# PAGE2-BLE_POWER_LORA.net
KiCad netlist of a schematic drawn in Altium Designer
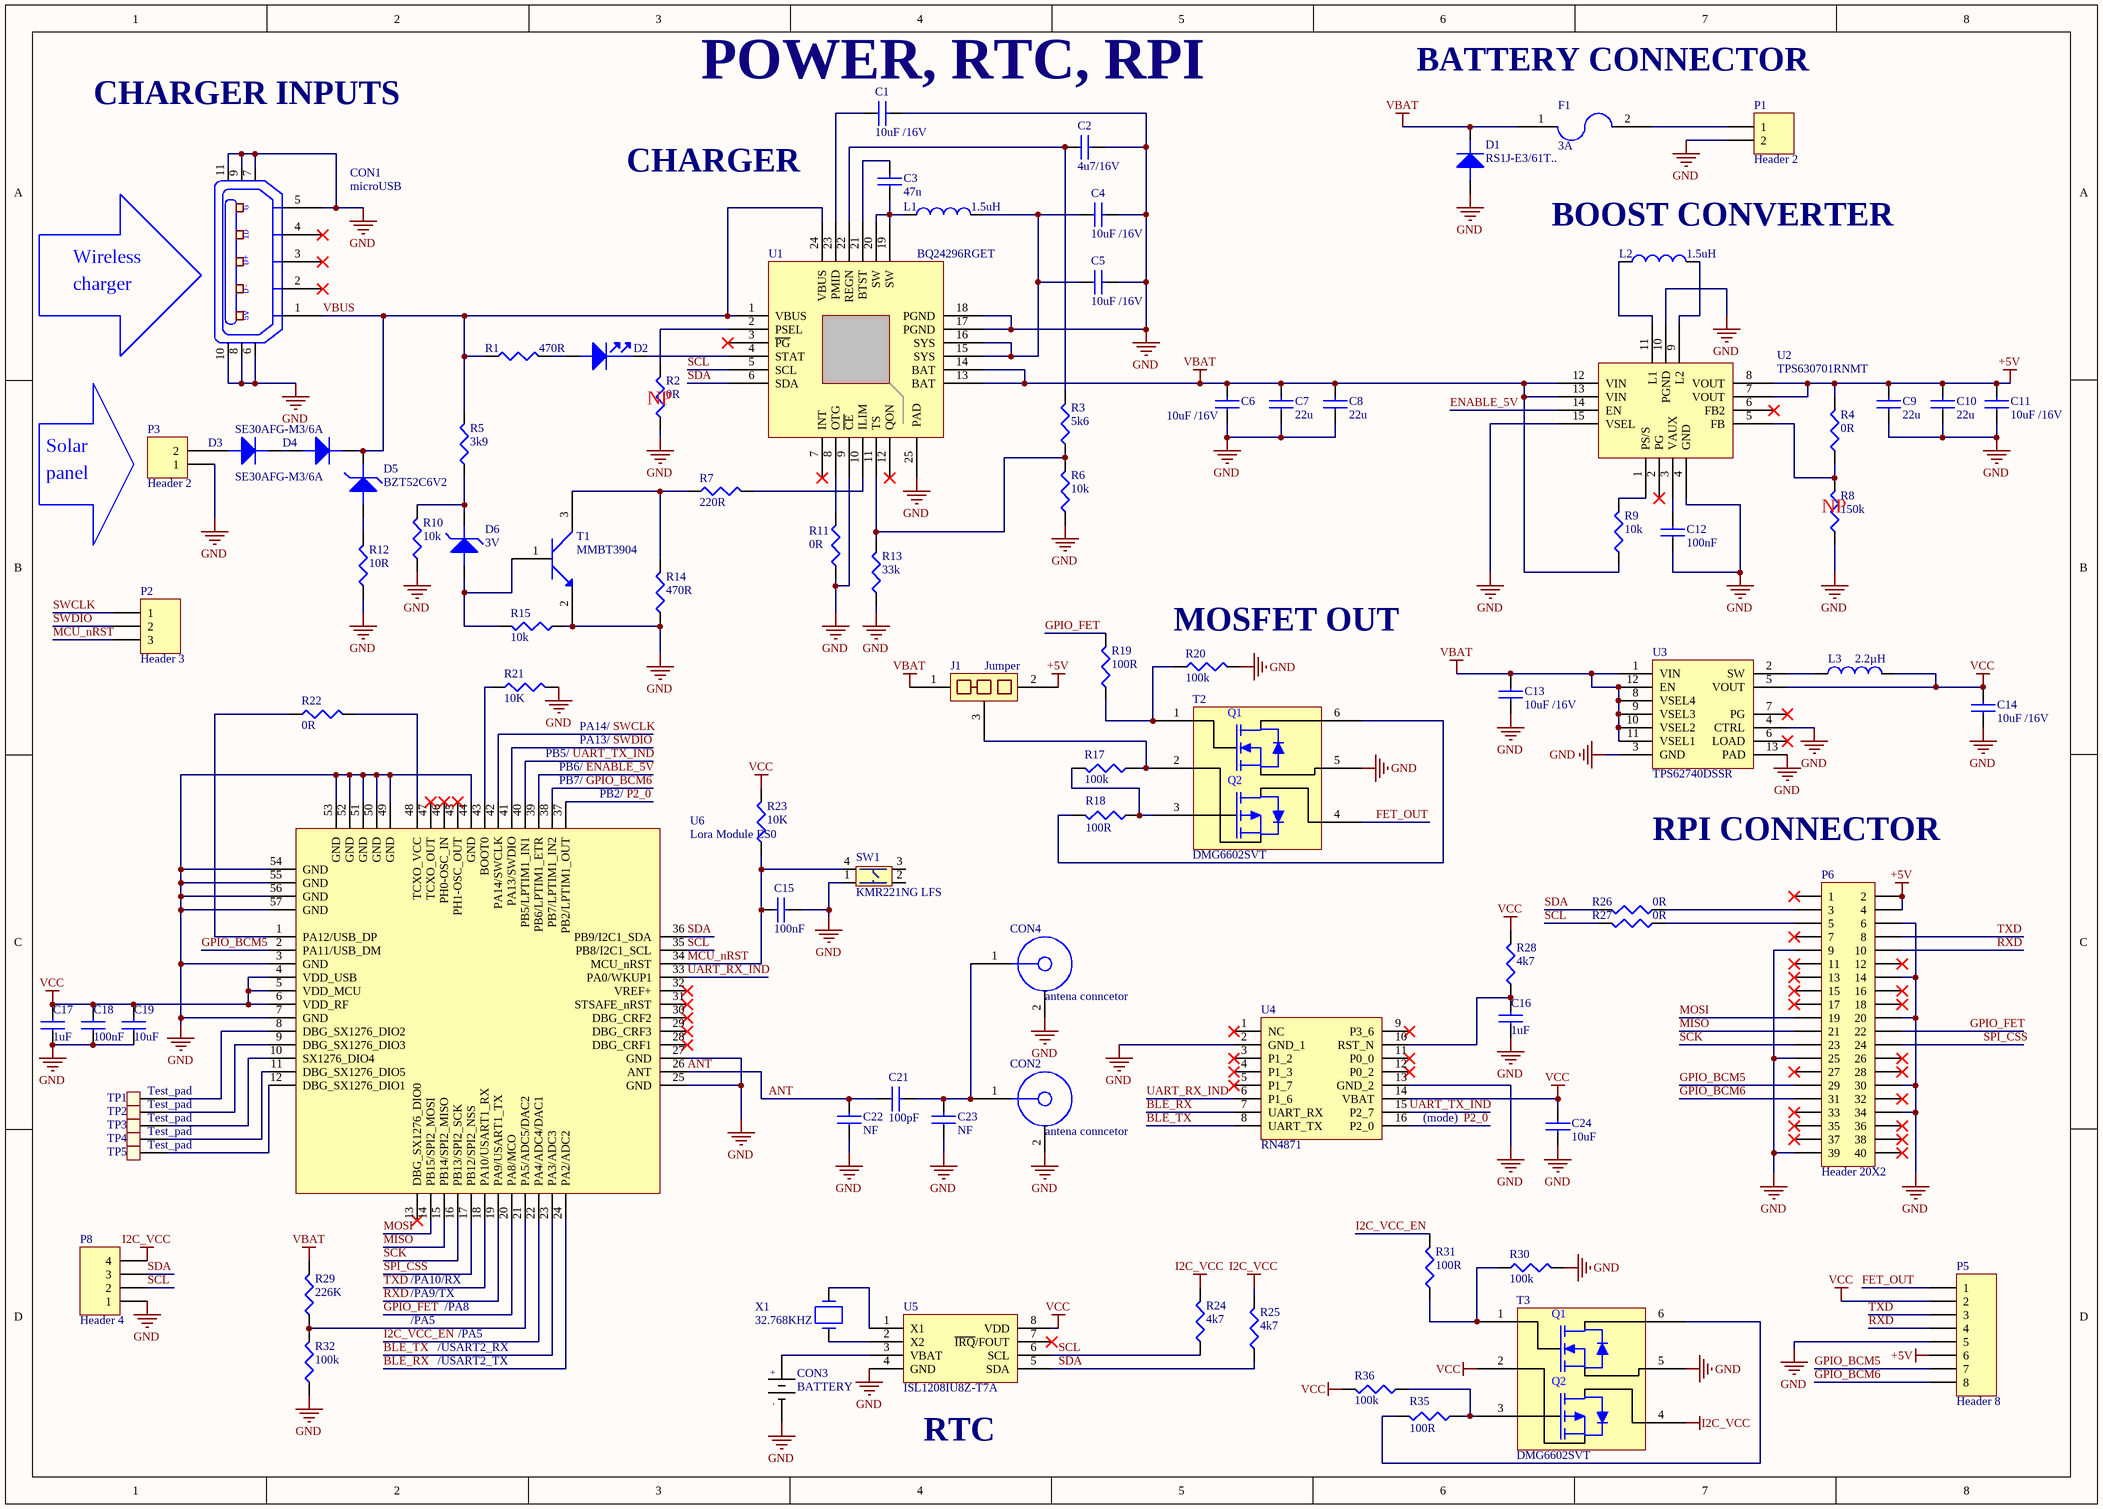
[diagram p0: PAGE2-BLE, POWER, LORA.SchDoc]

(export (version "E")
  (design (tool "Eeschema 10.0.6"))
  (components
    (comp (ref "C1")
      (value "10uF /16V")
      (footprint "CAP0805")
      (description "TDK - CGA4J1X5R1C106K125AC - CAP, MLCC, X5R, 10UF, 16V, 0805")
      (fields
        (field (name "MANUFACTURER") "TDK")
        (field (name "MANUFACTURER PART NUMBER") "CGA4J1X5R1C106K125AC")
      )
      (libsource (lib "Capacitors") (part "10uF /16V"))
    )
    (comp (ref "C2")
      (value "4u7/16V")
      (footprint "CAP0603")
      (description "MURATA - GRM188R61C475KAAJD - CAP, MLCC, X5R, 4.7UF, 16V, 0603")
      (fields
        (field (name "MANUFACTURER") "MURATA")
        (field (name "MANUFACTURER PART NUMBER") "GRM188R61C475KAAJD")
      )
      (libsource (lib "Capacitors") (part "4u7  16V 0603"))
    )
    (comp (ref "C3")
      (value "47n")
      (footprint "CAP0603")
      (description "MULTICOMP - MC0603B473K500CT - CAP, MLCC, X7R, 47NF, 50V, 0603")
      (fields
        (field (name "MANUFACTURER") "MULTICOMP")
        (field (name "MANUFACTURER PART NUMBER") "MC0603B473K500CT")
      )
      (libsource (lib "Capacitors") (part "47nF / 50V"))
    )
    (comp (ref "C4")
      (value "10uF /16V")
      (footprint "CAP0805")
      (description "TDK - CGA4J1X5R1C106K125AC - CAP, MLCC, X5R, 10UF, 16V, 0805")
      (fields
        (field (name "MANUFACTURER") "TDK")
        (field (name "MANUFACTURER PART NUMBER") "CGA4J1X5R1C106K125AC")
      )
      (libsource (lib "Capacitors") (part "10uF /16V"))
    )
    (comp (ref "C5")
      (value "10uF /16V")
      (footprint "CAP0805")
      (description "TDK - CGA4J1X5R1C106K125AC - CAP, MLCC, X5R, 10UF, 16V, 0805")
      (fields
        (field (name "MANUFACTURER") "TDK")
        (field (name "MANUFACTURER PART NUMBER") "CGA4J1X5R1C106K125AC")
      )
      (libsource (lib "Capacitors") (part "10uF /16V"))
    )
    (comp (ref "C6")
      (value "10uF /16V")
      (footprint "CAP0805")
      (description "TDK - CGA4J1X5R1C106K125AC - CAP, MLCC, X5R, 10UF, 16V, 0805")
      (fields
        (field (name "MANUFACTURER") "TDK")
        (field (name "MANUFACTURER PART NUMBER") "CGA4J1X5R1C106K125AC")
      )
      (libsource (lib "Capacitors") (part "10uF /16V"))
    )
    (comp (ref "C7")
      (value "22u")
      (footprint "CAP0805")
      (description "MULTICOMP - MC0805X226M6R3CT - CAP, MLCC, X5R, 22UF, 0805")
      (fields
        (field (name "MANUFACTURER") "MULTICOMP")
        (field (name "MANUFACTURER PART NUMBER") "MC0805X226M6R3CT")
      )
      (libsource (lib "Capacitors") (part "22u 6.3V 0805"))
    )
    (comp (ref "C8")
      (value "22u")
      (footprint "CAP0805")
      (description "MULTICOMP - MC0805X226M6R3CT - CAP, MLCC, X5R, 22UF, 0805")
      (fields
        (field (name "MANUFACTURER") "MULTICOMP")
        (field (name "MANUFACTURER PART NUMBER") "MC0805X226M6R3CT")
      )
      (libsource (lib "Capacitors") (part "22u 6.3V 0805"))
    )
    (comp (ref "C9")
      (value "22u")
      (footprint "CAP0805")
      (description "MULTICOMP - MC0805X226M6R3CT - CAP, MLCC, X5R, 22UF, 0805")
      (fields
        (field (name "MANUFACTURER") "MULTICOMP")
        (field (name "MANUFACTURER PART NUMBER") "MC0805X226M6R3CT")
      )
      (libsource (lib "Capacitors") (part "22u 6.3V 0805"))
    )
    (comp (ref "C10")
      (value "22u")
      (footprint "CAP0805")
      (description "MULTICOMP - MC0805X226M6R3CT - CAP, MLCC, X5R, 22UF, 0805")
      (fields
        (field (name "MANUFACTURER") "MULTICOMP")
        (field (name "MANUFACTURER PART NUMBER") "MC0805X226M6R3CT")
      )
      (libsource (lib "Capacitors") (part "22u 6.3V 0805"))
    )
    (comp (ref "C11")
      (value "10uF /16V")
      (footprint "CAP0805")
      (description "TDK - CGA4J1X5R1C106K125AC - CAP, MLCC, X5R, 10UF, 16V, 0805")
      (fields
        (field (name "MANUFACTURER") "TDK")
        (field (name "MANUFACTURER PART NUMBER") "CGA4J1X5R1C106K125AC")
      )
      (libsource (lib "Capacitors") (part "10uF /16V"))
    )
    (comp (ref "C12")
      (value "100nF")
      (footprint "CAP0603")
      (description "MURATA - GRM188R71C104KA01J - CAP, MLCC, X7R, 0.1UF, 16V, 0603")
      (fields
        (field (name "MANUFACTURER") "MURATA")
        (field (name "MANUFACTURER PART NUMBER") "GRM188R71C104KA01J")
      )
      (libsource (lib "Capacitors") (part "100nF"))
    )
    (comp (ref "C13")
      (value "10uF /16V")
      (footprint "CAP0805")
      (description "TDK - CGA4J1X5R1C106K125AC - CAP, MLCC, X5R, 10UF, 16V, 0805")
      (fields
        (field (name "MANUFACTURER") "TDK")
        (field (name "MANUFACTURER PART NUMBER") "CGA4J1X5R1C106K125AC")
      )
      (libsource (lib "Capacitors") (part "10uF /16V"))
    )
    (comp (ref "C14")
      (value "10uF /16V")
      (footprint "CAP0805")
      (description "TDK - CGA4J1X5R1C106K125AC - CAP, MLCC, X5R, 10UF, 16V, 0805")
      (fields
        (field (name "MANUFACTURER") "TDK")
        (field (name "MANUFACTURER PART NUMBER") "CGA4J1X5R1C106K125AC")
      )
      (libsource (lib "Capacitors") (part "10uF /16V"))
    )
    (comp (ref "C15")
      (value "100nF")
      (footprint "CAP0603")
      (description "MURATA - GRM188R71C104KA01J - CAP, MLCC, X7R, 0.1UF, 16V, 0603")
      (fields
        (field (name "MANUFACTURER") "MURATA")
        (field (name "MANUFACTURER PART NUMBER") "GRM188R71C104KA01J")
      )
      (libsource (lib "Capacitors") (part "100nF"))
    )
    (comp (ref "C16")
      (value "1uF")
      (footprint "CAP0603")
      (description "MURATA - GRM188R61H105KAALD - CAP, MLCC, X5R, 1UF, 50V, 0603")
      (fields
        (field (name "MANUFACTURER") "MURATA")
        (field (name "MANUFACTURER PART NUMBER") "GRM188R61H105KAALD")
      )
      (libsource (lib "Capacitors") (part "1uF"))
    )
    (comp (ref "C17")
      (value "1uF")
      (footprint "CAP0603")
      (description "MURATA - GRM188R61H105KAALD - CAP, MLCC, X5R, 1UF, 50V, 0603")
      (fields
        (field (name "MANUFACTURER") "MURATA")
        (field (name "MANUFACTURER PART NUMBER") "GRM188R61H105KAALD")
      )
      (libsource (lib "Capacitors") (part "1uF"))
    )
    (comp (ref "C18")
      (value "100nF")
      (footprint "CAP0603")
      (description "MURATA - GRM188R71C104KA01J - CAP, MLCC, X7R, 0.1UF, 16V, 0603")
      (fields
        (field (name "MANUFACTURER") "MURATA")
        (field (name "MANUFACTURER PART NUMBER") "GRM188R71C104KA01J")
      )
      (libsource (lib "Capacitors") (part "100nF"))
    )
    (comp (ref "C19")
      (value "10uF")
      (footprint "CAP0603")
      (description "10uf/0603/20%")
      (fields
        (field (name "MANUFACTURER") "KEMET")
        (field (name "MANUFACTURER PART NUMBER") "C0603C106M8PACTU")
      )
      (libsource (lib "pira-smart-schlib") (part "10uF"))
    )
    (comp (ref "C21")
      (value "100pF")
      (footprint "CAP0402")
      (description "Cap Ceramic 100pF 50V X7R 10% SMD 0402 125C T/R")
      (fields
        (field (name "MANUFACTURER") "KEMET")
        (field (name "MANUFACTURER PART NUMBER") "C0402C101K5RACTU")
      )
      (libsource (lib "Capacitors") (part "100pF/0402"))
    )
    (comp (ref "C22")
      (value "NF")
      (footprint "CAP0402")
      (description "Cap 0402 footprint only")
      (libsource (lib "pira-smart-schlib") (part "CAP0402"))
    )
    (comp (ref "C23")
      (value "NF")
      (footprint "CAP0402")
      (description "Cap 0402 footprint only")
      (libsource (lib "pira-smart-schlib") (part "CAP0402"))
    )
    (comp (ref "C24")
      (value "10uF")
      (footprint "CAP0603")
      (description "10uf/0603/20%")
      (fields
        (field (name "MANUFACTURER") "KEMET")
        (field (name "MANUFACTURER PART NUMBER") "C0603C106M8PACTU")
      )
      (libsource (lib "pira-smart-schlib") (part "10uF"))
    )
    (comp (ref "CON1")
      (value "microUSB")
      (footprint "microUSB-CHINA")
      (libsource (lib "USBConLibSCH") (part "Micro USB CHINA 1"))
    )
    (comp (ref "CON2")
      (value "antena conncetor")
      (footprint "ufl connector smd")
      (description "CONN UMC JACK STR 50 OHM SMD")
      (fields
        (field (name "MANUFACTURER") "Hirose")
        (field (name "MANUFACTURER PART NUMBER") "U.FL-R-SMT-1(10)")
      )
      (libsource (lib "pira-smart-schlib") (part "Antena copnnector"))
    )
    (comp (ref "CON3")
      (value "BATTERY")
      (footprint "CR-2032/VCN")
      (description "BATT LITH COIN 3V CELL PC PINS")
      (fields
        (field (name "MANUFACTURER") "Panasonic BSG")
        (field (name "MANUFACTURER PART NUMBER") "CR-2032/VCN")
      )
      (libsource (lib "pira-smart-schlib") (part "CR-2032/VCN"))
    )
    (comp (ref "CON4")
      (value "antena conncetor")
      (footprint "ufl connector smd")
      (description "CONN UMC JACK STR 50 OHM SMD")
      (fields
        (field (name "MANUFACTURER") "Hirose")
        (field (name "MANUFACTURER PART NUMBER") "U.FL-R-SMT-1(10)")
      )
      (libsource (lib "pira-smart-schlib") (part "Antena copnnector"))
    )
    (comp (ref "D1")
      (value "RS1J-E3/61T..")
      (footprint "SMC/DO-214AC")
      (description "VISHAY - RS1J-E3/61T.. - DIODE, FAST, 1A, 600V, SMD")
      (fields (field (name "MANUFACTURER") "VISHAY"))
      (libsource (lib "Diodes") (part "RS1J-E3/61T.."))
    )
    (comp (ref "D2")
      (value "LED RED")
      (footprint "LED0603")
      (description "BROADCOM LIMITED - HSMS-C190 - LED, RED, 10MCD, 626NM")
      (fields
        (field (name "MANUFACTURER") "BROADCOM LIMITED")
        (field (name "MANUFACTURER PART NUMBER") "HSMS-C190")
      )
      (libsource (lib "Diodes") (part "LED RED"))
    )
    (comp (ref "D3")
      (value "SE30AFG-M3/6A")
      (footprint "SODFL127P600-8N")
      (description "VISHAY - SE30AFG-M3/6A - RECTIFIER, ESD, 400V, 3A, DO-221AC")
      (fields (field (name "MANUFACTURER") "VISHAY"))
      (libsource (lib "Diodes_Schlib") (part "SE30AFG-M3/6A"))
    )
    (comp (ref "D4")
      (value "SE30AFG-M3/6A")
      (footprint "SODFL127P600-8N")
      (description "VISHAY - SE30AFG-M3/6A - RECTIFIER, ESD, 400V, 3A, DO-221AC")
      (fields (field (name "MANUFACTURER") "VISHAY"))
      (libsource (lib "Diodes_Schlib") (part "SE30AFG-M3/6A"))
    )
    (comp (ref "D5")
      (value "BZT52C6V2")
      (footprint "SOD123")
      (description "DIODES INC. - BZT52C6V2 - DIODE, ZENER, 6.2V, 0.5W, SOD-123")
      (fields (field (name "MANUFACTURER") "DIODES INC."))
      (libsource (lib "Diodes_Schlib") (part "BZT52C6V2"))
    )
    (comp (ref "D6")
      (value "3V")
      (footprint "SOD-323 2L")
      (description "ON SEMICONDUCTOR - MM3Z3V0T1G - ZENER DIODE, 200MW, 3V, SOD-323")
      (fields
        (field (name "MANUFACTURER") "ON SEMICONDUCTOR")
        (field (name "MANUFACTURER PART NUMBER") "MM3Z3V0T1G")
      )
      (libsource (lib "Diodes") (part "MM3Z3V0T1G"))
    )
    (comp (ref "F1")
      (value "3A")
      (footprint "Chip2PinSM127P600-8N")
      (description "LITTELFUSE - MINISMDC150F/24-2 - POLYSWITCH, SMD, 1812, 1.5A")
      (fields
        (field (name "MANUFACTURER") "LITTELFUSE")
        (field (name "MANUFACTURER PART NUMBER") "MINISMDC150F/24-2")
      )
      (libsource (lib "Fuse_SchLib") (part "PTC FUSE 3A"))
    )
    (comp (ref "J1") (value "Jumper") (footprint "JUMPER_NC") (libsource (lib "Jumper") (part "Jumper")))
    (comp (ref "L1")
      (value "1.5uH")
      (footprint "FDSD0402")
      (description "MURATA - FDSD0420-H-1R5M=P3 - INDUCTOR, SHIELDED, 1.5UH, 5.1A, 20%")
      (fields
        (field (name "MANUFACTURER") "MURATA")
        (field (name "MANUFACTURER PART NUMBER") "FDSD0420-H-1R5M=P3")
      )
      (libsource (lib "Inductors") (part "1.5uH 5.1A"))
    )
    (comp (ref "L2")
      (value "1.5uH")
      (footprint "FDSD0402")
      (description "MURATA - FDSD0420-H-1R5M=P3 - INDUCTOR, SHIELDED, 1.5UH, 5.1A, 20%")
      (fields
        (field (name "MANUFACTURER") "MURATA")
        (field (name "MANUFACTURER PART NUMBER") "FDSD0420-H-1R5M=P3")
      )
      (libsource (lib "Inductors") (part "1.5uH 5.1A"))
    )
    (comp (ref "L3")
      (value "2.2µH")
      (footprint "INDC2214X15N")
      (description "Fixed Inductors PFL2015 Shld Power 2.2 uH 20 % 1 A")
      (fields
        (field (name "MANUFACTURER") "Coilcraft")
        (field (name "MANUFACTURER PART NUMBER") "PFL2015-222MEB")
      )
      (libsource (lib "pira-smart-schlib") (part "PFL2015-222MEB"))
    )
    (comp (ref "P1")
      (value "Header 2")
      (footprint "HDR1X2")
      (description "Header, 2-Pin")
      (fields (field (name "PUBLISHER") "Altium Limited"))
      (libsource (lib "Miscellaneous Connectors") (part "Header 2"))
    )
    (comp (ref "P2")
      (value "Header 3")
      (footprint "HDR1X3")
      (description "Header, 3-Pin")
      (fields (field (name "PUBLISHER") "Altium Limited"))
      (libsource (lib "Miscellaneous Connectors") (part "Header 3"))
    )
    (comp (ref "P3")
      (value "Header 2")
      (footprint "HDR1X2")
      (description "Header, 2-Pin")
      (fields (field (name "PUBLISHER") "Altium Limited"))
      (libsource (lib "") (part "Header 2_1"))
    )
    (comp (ref "P5")
      (value "Header 8")
      (footprint "HDR1X8")
      (description "Header, 8-Pin")
      (fields (field (name "PUBLISHER") "Altium Limited"))
      (libsource (lib "Miscellaneous Connectors") (part "Header 8"))
    )
    (comp (ref "P6")
      (value "Header 20X2")
      (footprint "HDR2X20")
      (description "Header, 20-Pin, Dual row")
      (fields (field (name "PUBLISHER") "Altium Limited"))
      (libsource (lib "Miscellaneous Connectors") (part "Header 20X2"))
    )
    (comp (ref "P8")
      (value "Header 4")
      (footprint "HDR1X4")
      (description "Header, 4-Pin")
      (fields (field (name "PUBLISHER") "Altium Limited"))
      (libsource (lib "Miscellaneous Connectors") (part "Header 4"))
    )
    (comp (ref "R1")
      (value "470R")
      (footprint "RES0603")
      (description "MULTICOMP - MCMR06X471 JTL - RES, CERAMIC, 470R, 5%, 0.1W, 0603")
      (fields
        (field (name "MANUFACTURER") "MULTICOMP")
        (field (name "MANUFACTURER PART NUMBER") "MCMR06X471 JTL")
      )
      (libsource (lib "Resistors") (part "470R"))
    )
    (comp (ref "R2")
      (value "0R")
      (footprint "RES0603")
      (description "BOURNS - CR0603-J/-000ELF - RES, THICK FILM, 0R, 5%, 0.1W, 0603")
      (fields
        (field (name "MANUFACTURER") "BOURNS")
        (field (name "MANUFACTURER PART NUMBER") "CR0603-J/-000ELF")
      )
      (libsource (lib "Resistors") (part "0R"))
    )
    (comp (ref "R3")
      (value "5k6")
      (footprint "RES0603")
      (description "MULTICOMP - MCMR06X5601FTL - RES, CERAMIC, 5K6, 1%, 0.1W, 0603")
      (fields
        (field (name "MANUFACTURER") "MULTICOMP")
        (field (name "MANUFACTURER PART NUMBER") "MCMR06X5601FTL")
      )
      (libsource (lib "Resistors") (part "5k6"))
    )
    (comp (ref "R4")
      (value "0R")
      (footprint "RES0603")
      (description "BOURNS - CR0603-J/-000ELF - RES, THICK FILM, 0R, 5%, 0.1W, 0603")
      (fields
        (field (name "MANUFACTURER") "BOURNS")
        (field (name "MANUFACTURER PART NUMBER") "CR0603-J/-000ELF")
      )
      (libsource (lib "Resistors") (part "0R"))
    )
    (comp (ref "R5")
      (value "3k9")
      (footprint "RES0603")
      (description "MULTICOMP - MCWR06X3901FTL - RES, THICK FILM, 3K9, 1%, 0.1W, 0603")
      (fields
        (field (name "MANUFACTURER") "MULTICOMP")
        (field (name "MANUFACTURER PART NUMBER") "MCWR06X3901FTL")
      )
      (libsource (lib "Resistors") (part "3k9"))
    )
    (comp (ref "R6")
      (value "10k")
      (footprint "RES0603")
      (description "MULTICOMP - MCMR06X103 JTL - RES, CERAMIC, 10K, 5%, 0.1W, 0603")
      (fields
        (field (name "MANUFACTURER") "MULTICOMP")
        (field (name "MANUFACTURER PART NUMBER") "MCMR06X103 JTL")
      )
      (libsource (lib "Resistors") (part "10k"))
    )
    (comp (ref "R7")
      (value "220R")
      (footprint "RES0603")
      (description "MULTICOMP - MCWR06X2200FTL - RES, THICK FILM, 220R, 1%, 0.1W, 0603")
      (fields
        (field (name "MANUFACTURER") "MULTICOMP")
        (field (name "MANUFACTURER PART NUMBER") "MCWR06X2200FTL")
      )
      (libsource (lib "Resistors") (part "220R"))
    )
    (comp (ref "R8")
      (value "150k")
      (footprint "RES0603")
      (description "MULTICOMP - MCWR06X1503FTL - RES, THICK FILM, 150KOHM, 1%, 0.1W")
      (fields
        (field (name "MANUFACTURER") "MULTICOMP")
        (field (name "MANUFACTURER PART NUMBER") "MCWR06X1503FTL")
      )
      (libsource (lib "Resistors") (part "150k"))
    )
    (comp (ref "R9")
      (value "10k")
      (footprint "RES0603")
      (description "MULTICOMP - MCMR06X103 JTL - RES, CERAMIC, 10K, 5%, 0.1W, 0603")
      (fields
        (field (name "MANUFACTURER") "MULTICOMP")
        (field (name "MANUFACTURER PART NUMBER") "MCMR06X103 JTL")
      )
      (libsource (lib "Resistors") (part "10k"))
    )
    (comp (ref "R10")
      (value "10k")
      (footprint "RES0603")
      (description "MULTICOMP - MCMR06X103 JTL - RES, CERAMIC, 10K, 5%, 0.1W, 0603")
      (fields
        (field (name "MANUFACTURER") "MULTICOMP")
        (field (name "MANUFACTURER PART NUMBER") "MCMR06X103 JTL")
      )
      (libsource (lib "Resistors") (part "10k"))
    )
    (comp (ref "R11")
      (value "0R")
      (footprint "RES0603")
      (description "BOURNS - CR0603-J/-000ELF - RES, THICK FILM, 0R, 5%, 0.1W, 0603")
      (fields
        (field (name "MANUFACTURER") "BOURNS")
        (field (name "MANUFACTURER PART NUMBER") "CR0603-J/-000ELF")
      )
      (libsource (lib "Resistors") (part "0R"))
    )
    (comp (ref "R12")
      (value "10R")
      (footprint "RES0603")
      (description "VISHAY - RCA060310R0FKEA - RES, AUTO, THICK FILM, 10R, 1%, 0603")
      (fields
        (field (name "MANUFACTURER") "VISHAY")
        (field (name "MANUFACTURER PART NUMBER") "RCA060310R0FKEA")
      )
      (libsource (lib "Resistors") (part "10R"))
    )
    (comp (ref "R13")
      (value "33k")
      (footprint "RES0603")
      (description "MULTICOMP - MCWR06X3302FTL - RES, THICK FILM, 33K, 1%, 0.1W, 0603")
      (fields
        (field (name "MANUFACTURER") "MULTICOMP")
        (field (name "MANUFACTURER PART NUMBER") "MCWR06X3302FTL")
      )
      (libsource (lib "Resistors") (part "33k"))
    )
    (comp (ref "R14")
      (value "470R")
      (footprint "RES0603")
      (description "MULTICOMP - MCMR06X471 JTL - RES, CERAMIC, 470R, 5%, 0.1W, 0603")
      (fields
        (field (name "MANUFACTURER") "MULTICOMP")
        (field (name "MANUFACTURER PART NUMBER") "MCMR06X471 JTL")
      )
      (libsource (lib "Resistors") (part "470R"))
    )
    (comp (ref "R15")
      (value "10k")
      (footprint "RES0603")
      (description "MULTICOMP - MCMR06X103 JTL - RES, CERAMIC, 10K, 5%, 0.1W, 0603")
      (fields
        (field (name "MANUFACTURER") "MULTICOMP")
        (field (name "MANUFACTURER PART NUMBER") "MCMR06X103 JTL")
      )
      (libsource (lib "Resistors") (part "10k"))
    )
    (comp (ref "R17")
      (value "100k")
      (footprint "RES0603")
      (description "MULTICOMP - MCMR06X104 JTL - RES, CERAMIC, 100K, 5%, 0.1W, 0603")
      (fields
        (field (name "MANUFACTURER") "MULTICOMP")
        (field (name "MANUFACTURER PART NUMBER") "MCMR06X104 JTL")
      )
      (libsource (lib "Resistors") (part "100k"))
    )
    (comp (ref "R18")
      (value "100R")
      (footprint "RES0603")
      (description "MULTICOMP - MC0063W06031100R - RES, THICK FILM, 100R, 1%, 0.063W, 0603")
      (fields
        (field (name "MANUFACTURER") "MULTICOMP")
        (field (name "MANUFACTURER PART NUMBER") "MC0063W06031100R")
      )
      (libsource (lib "Resistors") (part "100R"))
    )
    (comp (ref "R19")
      (value "100R")
      (footprint "RES0603")
      (description "MULTICOMP - MC0063W06031100R - RES, THICK FILM, 100R, 1%, 0.063W, 0603")
      (fields
        (field (name "MANUFACTURER") "MULTICOMP")
        (field (name "MANUFACTURER PART NUMBER") "MC0063W06031100R")
      )
      (libsource (lib "Resistors") (part "100R"))
    )
    (comp (ref "R20")
      (value "100k")
      (footprint "RES0603")
      (description "MULTICOMP - MCMR06X104 JTL - RES, CERAMIC, 100K, 5%, 0.1W, 0603")
      (fields
        (field (name "MANUFACTURER") "MULTICOMP")
        (field (name "MANUFACTURER PART NUMBER") "MCMR06X104 JTL")
      )
      (libsource (lib "Resistors") (part "100k"))
    )
    (comp (ref "R21")
      (value "10K")
      (footprint "RES0603")
      (description "10K resistor")
      (libsource (lib "pira-smart-schlib") (part "10K"))
    )
    (comp (ref "R22")
      (value "0R")
      (footprint "RES0603")
      (description "Zero ohm resistor")
      (libsource (lib "pira-smart-schlib") (part "0R"))
    )
    (comp (ref "R23")
      (value "10K")
      (footprint "RES0603")
      (description "10K resistor")
      (libsource (lib "pira-smart-schlib") (part "10K"))
    )
    (comp (ref "R24")
      (value "4k7")
      (footprint "RES0603")
      (description "MULTICOMP - MCMR06X4701FTL - RES, CERAMIC, 4K7, 1%, 0.1W, 0603")
      (fields
        (field (name "MANUFACTURER") "MULTICOMP")
        (field (name "MANUFACTURER PART NUMBER") "MCMR06X4701FTL")
      )
      (libsource (lib "Resistors") (part "4k7"))
    )
    (comp (ref "R25")
      (value "4k7")
      (footprint "RES0603")
      (description "MULTICOMP - MCMR06X4701FTL - RES, CERAMIC, 4K7, 1%, 0.1W, 0603")
      (fields
        (field (name "MANUFACTURER") "MULTICOMP")
        (field (name "MANUFACTURER PART NUMBER") "MCMR06X4701FTL")
      )
      (libsource (lib "Resistors") (part "4k7"))
    )
    (comp (ref "R26")
      (value "0R")
      (footprint "RES0603")
      (description "BOURNS - CR0603-J/-000ELF - RES, THICK FILM, 0R, 5%, 0.1W, 0603")
      (fields
        (field (name "MANUFACTURER") "BOURNS")
        (field (name "MANUFACTURER PART NUMBER") "CR0603-J/-000ELF")
      )
      (libsource (lib "Resistors") (part "0R"))
    )
    (comp (ref "R27")
      (value "0R")
      (footprint "RES0603")
      (description "BOURNS - CR0603-J/-000ELF - RES, THICK FILM, 0R, 5%, 0.1W, 0603")
      (fields
        (field (name "MANUFACTURER") "BOURNS")
        (field (name "MANUFACTURER PART NUMBER") "CR0603-J/-000ELF")
      )
      (libsource (lib "Resistors") (part "0R"))
    )
    (comp (ref "R28")
      (value "4k7")
      (footprint "RES0603")
      (description "MULTICOMP - MCMR06X4701FTL - RES, CERAMIC, 4K7, 1%, 0.1W, 0603")
      (fields
        (field (name "MANUFACTURER") "MULTICOMP")
        (field (name "MANUFACTURER PART NUMBER") "MCMR06X4701FTL")
      )
      (libsource (lib "Resistors") (part "4k7"))
    )
    (comp (ref "R29")
      (value "226K")
      (footprint "RES0603")
      (description "Thick Film Resistors - SMD 1/10watt 226Kohms 1%")
      (fields
        (field (name "MANUFACTURER") "Vishay")
        (field (name "MANUFACTURER PART NUMBER") "CRCW0603226KFKEA")
      )
      (libsource (lib "pira-smart-schlib") (part "226K"))
    )
    (comp (ref "R30")
      (value "100k")
      (footprint "RES0603")
      (description "MULTICOMP - MCMR06X104 JTL - RES, CERAMIC, 100K, 5%, 0.1W, 0603")
      (fields
        (field (name "MANUFACTURER") "MULTICOMP")
        (field (name "MANUFACTURER PART NUMBER") "MCMR06X104 JTL")
      )
      (libsource (lib "Resistors") (part "100k"))
    )
    (comp (ref "R31")
      (value "100R")
      (footprint "RES0603")
      (description "MULTICOMP - MC0063W06031100R - RES, THICK FILM, 100R, 1%, 0.063W, 0603")
      (fields
        (field (name "MANUFACTURER") "MULTICOMP")
        (field (name "MANUFACTURER PART NUMBER") "MC0063W06031100R")
      )
      (libsource (lib "Resistors") (part "100R"))
    )
    (comp (ref "R32")
      (value "100k")
      (footprint "RES0603")
      (description "MULTICOMP - MCMR06X104 JTL - RES, CERAMIC, 100K, 5%, 0.1W, 0603")
      (fields
        (field (name "MANUFACTURER") "MULTICOMP")
        (field (name "MANUFACTURER PART NUMBER") "MCMR06X104 JTL")
      )
      (libsource (lib "Resistors") (part "100k"))
    )
    (comp (ref "R35")
      (value "100R")
      (footprint "RES0603")
      (description "MULTICOMP - MC0063W06031100R - RES, THICK FILM, 100R, 1%, 0.063W, 0603")
      (fields
        (field (name "MANUFACTURER") "MULTICOMP")
        (field (name "MANUFACTURER PART NUMBER") "MC0063W06031100R")
      )
      (libsource (lib "Resistors") (part "100R"))
    )
    (comp (ref "R36")
      (value "100k")
      (footprint "RES0603")
      (description "MULTICOMP - MCMR06X104 JTL - RES, CERAMIC, 100K, 5%, 0.1W, 0603")
      (fields
        (field (name "MANUFACTURER") "MULTICOMP")
        (field (name "MANUFACTURER PART NUMBER") "MCMR06X104 JTL")
      )
      (libsource (lib "Resistors") (part "100k"))
    )
    (comp (ref "SW1")
      (value "KMR221NG LFS")
      (footprint "Tactile button")
      (description "SWITCH TACTILE SPST-NO 0.05A 32V")
      (fields (field (name "MANUFACTURER") "ITT C&K") (field (name "MANUFACTURER PART NUMBER") "KMR221NGLFS"))
      (libsource (lib "pira-smart-schlib") (part "Tactile button"))
    )
    (comp (ref "T1")
      (value "MMBT3904")
      (footprint "SOT23127P600-8N")
      (description "ON SEMICONDUCTOR/FAIRCHILD - MMBT3904 - TRANSISTOR, NPN, SOT-23")
      (fields (field (name "MANUFACTURER") "ON SEMICONDUCTOR/FAIRCHILD"))
      (libsource (lib "PiRA-RTC-HAT-SchLib") (part "MMBT3904"))
    )
    (comp (ref "T2")
      (value "DMG6602SVT")
      (footprint "TSOT26")
      (description "DIODES INC. - DMG6602SVT - MOSFET, NP CH, , 30V, 3.4, ATSOT23")
      (fields (field (name "MANUFACTURER") "DIODES INC."))
      (libsource (lib "PiRA-RTC-HAT-PCB") (part "DMG6602SVT"))
    )
    (comp (ref "T3")
      (value "DMG6602SVT")
      (footprint "TSOT26")
      (description "DIODES INC. - DMG6602SVT - MOSFET, NP CH, , 30V, 3.4, ATSOT23")
      (fields (field (name "MANUFACTURER") "DIODES INC."))
      (libsource (lib "PiRA-RTC-HAT-PCB") (part "DMG6602SVT"))
    )
    (comp (ref "TP1")
      (value "Test_pad")
      (footprint "Test_pad")
      (libsource (lib "pira-smart-schlib") (part "Test_pad"))
    )
    (comp (ref "TP2")
      (value "Test_pad")
      (footprint "Test_pad")
      (libsource (lib "pira-smart-schlib") (part "Test_pad"))
    )
    (comp (ref "TP3")
      (value "Test_pad")
      (footprint "Test_pad")
      (libsource (lib "pira-smart-schlib") (part "Test_pad"))
    )
    (comp (ref "TP4")
      (value "Test_pad")
      (footprint "Test_pad")
      (libsource (lib "pira-smart-schlib") (part "Test_pad"))
    )
    (comp (ref "TP5")
      (value "Test_pad")
      (footprint "Test_pad")
      (libsource (lib "pira-smart-schlib") (part "Test_pad"))
    )
    (comp (ref "U1")
      (value "BQ24296RGET")
      (footprint "QFN4x4")
      (description "IC LI+ CHARGER PWR MGMT 24VQFN")
      (fields (field (name "MANUFACTURER") "Texas Instruments"))
      (libsource (lib "PiRA-RTC-HAT-SchLib") (part "BQ24296RGET"))
    )
    (comp (ref "U2")
      (value "TPS630701RNMT")
      (footprint "VQFN TPS")
      (description "TEXAS INSTRUMENTS - TPS630701RNMT - DC/DC CONV, BUCK-BOOST, 2.4MHZ, VQFN-15")
      (fields (field (name "MANUFACTURER") "TEXAS INSTRUMENTS"))
      (libsource (lib "PiRA-RTC-HAT-SchLib") (part "TPS630701RNMT"))
    )
    (comp (ref "U3")
      (value "TPS62740DSSR")
      (footprint "SON50P200X265_HS-13N")
      (description "Voltage Regulators - Switching Regulators 360-nA Iq SD Cnvtr w/ Intg Load Switch")
      (fields (field (name "MANUFACTURER") "Texas Instruments"))
      (libsource (lib "pira-smart-schlib") (part "TPS62740DSSR"))
    )
    (comp (ref "U4")
      (value "RN4871")
      (footprint "RN4871")
      (fields
        (field (name "MANUFACTURER") "Microchip")
        (field (name "MANUFACTURER PART NUMBER") "RN4871-V/RM118")
      )
      (libsource (lib "pira-smart-schlib") (part "RN4871-V/RM118"))
    )
    (comp (ref "U5")
      (value "ISL1208IU8Z-T7A")
      (footprint "TSOP65P500X110-8N")
      (description "IC RTC/CALENDAR I2C LP 8MSOP")
      (fields (field (name "MANUFACTURER") "Intersil"))
      (libsource (lib "pira-smart-schlib") (part "ISL1208IU8Z-T7A"))
    )
    (comp (ref "U6")
      (value "Lora Module ES0")
      (footprint "Lora Module ES0")
      (description "Lora Module Murata")
      (libsource (lib "pira-smart-schlib") (part "Lora Module Murata"))
    )
    (comp (ref "X1")
      (value "32.768KHZ")
      (footprint "LFXTAL009678")
      (description "CRYSTAL, 32.768KHZ, 12.5PF, SMD")
      (fields (field (name "MANUFACTURER") "IQD") (field (name "MANUFACTURER PART NUMBER") "LFXTAL009678"))
      (libsource (lib "pira-smart-schlib") (part "LFXTAL009678"))
    )
  )
  (nets
    (net (code "1") (name "+5V") (class "Default")
      (node (ref "C10") (pin "2") (pinfunction "2_2") (pintype "passive"))
      (node (ref "C11") (pin "2") (pinfunction "2_2") (pintype "passive"))
      (node (ref "C9") (pin "2") (pinfunction "2_2") (pintype "passive"))
      (node (ref "J1") (pin "2") (pinfunction "2_2") (pintype "open_collector"))
      (node (ref "P5") (pin "6") (pinfunction "6_6") (pintype "passive"))
      (node (ref "P6") (pin "2") (pinfunction "2_2") (pintype "passive"))
      (node (ref "P6") (pin "4") (pinfunction "4_4") (pintype "passive"))
      (node (ref "R4") (pin "2") (pinfunction "2_2") (pintype "passive"))
      (node (ref "U2") (pin "7") (pinfunction "VOUT_7") (pintype "open_collector"))
      (node (ref "U2") (pin "8") (pinfunction "VOUT_8") (pintype "open_collector"))
    )
    (net (code "2") (name "/ANT") (class "Default")
      (node (ref "C21") (pin "1") (pinfunction "1_1") (pintype "passive"))
      (node (ref "C22") (pin "2") (pinfunction "2_2") (pintype "passive"))
      (node (ref "U6") (pin "26") (pinfunction "ANT_26") (pintype "passive"))
    )
    (net (code "3") (name "/BLE_RX") (class "Default")
      (node (ref "U4") (pin "7") (pinfunction "UART_RX_7") (pintype "passive"))
      (node (ref "U6") (pin "24") (pinfunction "PA2/ADC2_24") (pintype "passive"))
    )
    (net (code "4") (name "/BLE_TX") (class "Default")
      (node (ref "U4") (pin "8") (pinfunction "UART_TX_8") (pintype "passive"))
      (node (ref "U6") (pin "23") (pinfunction "PA3/ADC3_23") (pintype "passive"))
    )
    (net (code "5") (name "/ENABLE_5V") (class "Default")
      (node (ref "U2") (pin "14") (pinfunction "EN_14") (pintype "open_collector"))
      (node (ref "U6") (pin "39") (pinfunction "PB6/LPTIM1_ETR_39") (pintype "passive"))
    )
    (net (code "6") (name "/FET_OUT") (class "Default")
      (node (ref "P5") (pin "1") (pinfunction "1_1") (pintype "passive"))
      (node (ref "T2") (pin "4") (pinfunction "D2_4") (pintype "open_collector"))
    )
    (net (code "7") (name "/GPIO_BCM5") (class "Default")
      (node (ref "P5") (pin "7") (pinfunction "7_7") (pintype "passive"))
      (node (ref "P6") (pin "29") (pinfunction "29_29") (pintype "passive"))
      (node (ref "U6") (pin "2") (pinfunction "PA11/USB_DM_2") (pintype "passive"))
    )
    (net (code "8") (name "/GPIO_BCM6") (class "Default")
      (node (ref "P5") (pin "8") (pinfunction "8_8") (pintype "passive"))
      (node (ref "P6") (pin "31") (pinfunction "31_31") (pintype "passive"))
      (node (ref "U6") (pin "38") (pinfunction "PB7/LPTIM1_IN2_38") (pintype "passive"))
    )
    (net (code "9") (name "/GPIO_FET") (class "Default")
      (node (ref "P6") (pin "22") (pinfunction "22_22") (pintype "passive"))
      (node (ref "R19") (pin "2") (pinfunction "2_2") (pintype "passive"))
      (node (ref "U6") (pin "20") (pinfunction "PA8/MCO_20") (pintype "passive"))
    )
    (net (code "10") (name "/I2C_VCC_EN") (class "Default")
      (node (ref "R31") (pin "2") (pinfunction "2_2") (pintype "passive"))
      (node (ref "U6") (pin "22") (pinfunction "PA4/ADC4/DAC1_22") (pintype "passive"))
    )
    (net (code "11") (name "/MCU_nRST") (class "Default")
      (node (ref "C15") (pin "1") (pinfunction "1_1") (pintype "passive"))
      (node (ref "P2") (pin "3") (pinfunction "3_3") (pintype "passive"))
      (node (ref "R23") (pin "1") (pinfunction "1_1") (pintype "passive"))
      (node (ref "SW1") (pin "4") (pinfunction "4_4") (pintype "passive"))
      (node (ref "U6") (pin "34") (pinfunction "MCU_nRST_34") (pintype "passive"))
    )
    (net (code "12") (name "/MISO") (class "Default")
      (node (ref "P6") (pin "21") (pinfunction "21_21") (pintype "passive"))
      (node (ref "U6") (pin "15") (pinfunction "PB14/SPI2_MISO_15") (pintype "passive"))
    )
    (net (code "13") (name "/MOSI") (class "Default")
      (node (ref "P6") (pin "19") (pinfunction "19_19") (pintype "passive"))
      (node (ref "U6") (pin "14") (pinfunction "PB15/SPI2_MOSI_14") (pintype "passive"))
    )
    (net (code "14") (name "/P2_0") (class "Default")
      (node (ref "U4") (pin "16") (pinfunction "P2_0_16") (pintype "passive"))
      (node (ref "U6") (pin "37") (pinfunction "PB2/LPTIM1_OUT_37") (pintype "passive"))
    )
    (net (code "15") (name "/RXD") (class "Default")
      (node (ref "P5") (pin "4") (pinfunction "4_4") (pintype "passive"))
      (node (ref "P6") (pin "10") (pinfunction "10_10") (pintype "passive"))
      (node (ref "U6") (pin "19") (pinfunction "PA9/USART1_TX_19") (pintype "passive"))
    )
    (net (code "16") (name "/SCK") (class "Default")
      (node (ref "P6") (pin "23") (pinfunction "23_23") (pintype "passive"))
      (node (ref "U6") (pin "16") (pinfunction "PB13/SPI2_SCK_16") (pintype "passive"))
    )
    (net (code "17") (name "/SCL") (class "Default")
      (node (ref "P8") (pin "2") (pinfunction "2_2") (pintype "passive"))
      (node (ref "R24") (pin "1") (pinfunction "1_1") (pintype "passive"))
      (node (ref "R27") (pin "2") (pinfunction "2_2") (pintype "passive"))
      (node (ref "U1") (pin "5") (pinfunction "SCL_5") (pintype "open_collector"))
      (node (ref "U5") (pin "6") (pinfunction "SCL_6") (pintype "open_collector"))
      (node (ref "U6") (pin "35") (pinfunction "PB8/I2C1_SCL_35") (pintype "passive"))
    )
    (net (code "18") (name "/SDA") (class "Default")
      (node (ref "P8") (pin "3") (pinfunction "3_3") (pintype "passive"))
      (node (ref "R25") (pin "1") (pinfunction "1_1") (pintype "passive"))
      (node (ref "R26") (pin "2") (pinfunction "2_2") (pintype "passive"))
      (node (ref "U1") (pin "6") (pinfunction "SDA_6") (pintype "open_collector"))
      (node (ref "U5") (pin "5") (pinfunction "SDA_5") (pintype "open_collector"))
      (node (ref "U6") (pin "36") (pinfunction "PB9/I2C1_SDA_36") (pintype "passive"))
    )
    (net (code "19") (name "/SPI_CSS") (class "Default")
      (node (ref "P6") (pin "24") (pinfunction "24_24") (pintype "passive"))
      (node (ref "U6") (pin "17") (pinfunction "PB12/SPI2_NSS_17") (pintype "passive"))
    )
    (net (code "20") (name "/SWCLK") (class "Default")
      (node (ref "P2") (pin "1") (pinfunction "1_1") (pintype "passive"))
      (node (ref "U6") (pin "42") (pinfunction "PA14/SWCLK_42") (pintype "passive"))
    )
    (net (code "21") (name "/SWDIO") (class "Default")
      (node (ref "P2") (pin "2") (pinfunction "2_2") (pintype "passive"))
      (node (ref "U6") (pin "41") (pinfunction "PA13/SWDIO_41") (pintype "passive"))
    )
    (net (code "22") (name "/TXD") (class "Default")
      (node (ref "P5") (pin "3") (pinfunction "3_3") (pintype "passive"))
      (node (ref "P6") (pin "8") (pinfunction "8_8") (pintype "passive"))
      (node (ref "U6") (pin "18") (pinfunction "PA10/USART1_RX_18") (pintype "passive"))
    )
    (net (code "23") (name "/UART_RX_IND") (class "Default")
      (node (ref "U4") (pin "6") (pinfunction "P1_6_6") (pintype "passive"))
      (node (ref "U6") (pin "33") (pinfunction "PA0/WKUP1_33") (pintype "passive"))
    )
    (net (code "24") (name "/UART_TX_IND") (class "Default")
      (node (ref "U4") (pin "15") (pinfunction "P2_7_15") (pintype "passive"))
      (node (ref "U6") (pin "40") (pinfunction "PB5/LPTIM1_IN1_40") (pintype "passive"))
    )
    (net (code "25") (name "/VBUS") (class "Default")
      (node (ref "CON1") (pin "1") (pinfunction "P1_1") (pintype "passive"))
      (node (ref "D4") (pin "1") (pinfunction "cathode_1") (pintype "passive"))
      (node (ref "D5") (pin "1") (pinfunction "cathode_1") (pintype "passive"))
      (node (ref "R1") (pin "1") (pinfunction "1_1") (pintype "passive"))
      (node (ref "R5") (pin "2") (pinfunction "2_2") (pintype "passive"))
      (node (ref "U1") (pin "1") (pinfunction "VBUS_1") (pintype "open_collector"))
      (node (ref "U1") (pin "24") (pinfunction "VBUS_24") (pintype "open_collector"))
    )
    (net (code "26") (name "GND") (class "Default")
      (node (ref "C1") (pin "2") (pinfunction "2_2") (pintype "passive"))
      (node (ref "C10") (pin "1") (pinfunction "1_1") (pintype "passive"))
      (node (ref "C11") (pin "1") (pinfunction "1_1") (pintype "passive"))
      (node (ref "C12") (pin "1") (pinfunction "1_1") (pintype "passive"))
      (node (ref "C13") (pin "1") (pinfunction "1_1") (pintype "passive"))
      (node (ref "C14") (pin "1") (pinfunction "1_1") (pintype "passive"))
      (node (ref "C15") (pin "2") (pinfunction "2_2") (pintype "passive"))
      (node (ref "C16") (pin "1") (pinfunction "1_1") (pintype "passive"))
      (node (ref "C17") (pin "1") (pinfunction "1_1") (pintype "passive"))
      (node (ref "C18") (pin "1") (pinfunction "1_1") (pintype "passive"))
      (node (ref "C19") (pin "1") (pinfunction "1_1") (pintype "passive"))
      (node (ref "C2") (pin "2") (pinfunction "2_2") (pintype "passive"))
      (node (ref "C22") (pin "1") (pinfunction "1_1") (pintype "passive"))
      (node (ref "C23") (pin "1") (pinfunction "1_1") (pintype "passive"))
      (node (ref "C24") (pin "1") (pinfunction "1_1") (pintype "passive"))
      (node (ref "C4") (pin "2") (pinfunction "2_2") (pintype "passive"))
      (node (ref "C5") (pin "2") (pinfunction "2_2") (pintype "passive"))
      (node (ref "C6") (pin "1") (pinfunction "1_1") (pintype "passive"))
      (node (ref "C7") (pin "1") (pinfunction "1_1") (pintype "passive"))
      (node (ref "C8") (pin "1") (pinfunction "1_1") (pintype "passive"))
      (node (ref "C9") (pin "1") (pinfunction "1_1") (pintype "passive"))
      (node (ref "CON1") (pin "10") (pinfunction "10_10") (pintype "passive"))
      (node (ref "CON1") (pin "11") (pinfunction "11_11") (pintype "passive"))
      (node (ref "CON1") (pin "5") (pinfunction "P5_5") (pintype "passive"))
      (node (ref "CON1") (pin "6") (pinfunction "6_6") (pintype "passive"))
      (node (ref "CON1") (pin "7") (pinfunction "7_7") (pintype "passive"))
      (node (ref "CON1") (pin "8") (pinfunction "8_8") (pintype "passive"))
      (node (ref "CON1") (pin "9") (pinfunction "9_9") (pintype "passive"))
      (node (ref "CON2") (pin "2") (pinfunction "2_2") (pintype "open_collector"))
      (node (ref "CON3") (pin "NEG") (pinfunction "NEG_NEG") (pintype "passive"))
      (node (ref "CON4") (pin "2") (pinfunction "2_2") (pintype "open_collector"))
      (node (ref "D1") (pin "2") (pinfunction "ANODE_2") (pintype "passive"))
      (node (ref "P1") (pin "2") (pinfunction "2_2") (pintype "passive"))
      (node (ref "P3") (pin "1") (pinfunction "1_1") (pintype "passive"))
      (node (ref "P5") (pin "5") (pinfunction "5_5") (pintype "passive"))
      (node (ref "P6") (pin "14") (pinfunction "14_14") (pintype "passive"))
      (node (ref "P6") (pin "20") (pinfunction "20_20") (pintype "passive"))
      (node (ref "P6") (pin "25") (pinfunction "25_25") (pintype "passive"))
      (node (ref "P6") (pin "30") (pinfunction "30_30") (pintype "passive"))
      (node (ref "P6") (pin "34") (pinfunction "34_34") (pintype "passive"))
      (node (ref "P6") (pin "39") (pinfunction "39_39") (pintype "passive"))
      (node (ref "P6") (pin "6") (pinfunction "6_6") (pintype "passive"))
      (node (ref "P6") (pin "9") (pinfunction "9_9") (pintype "passive"))
      (node (ref "P8") (pin "1") (pinfunction "1_1") (pintype "passive"))
      (node (ref "R10") (pin "1") (pinfunction "1_1") (pintype "passive"))
      (node (ref "R11") (pin "1") (pinfunction "1_1") (pintype "passive"))
      (node (ref "R12") (pin "1") (pinfunction "1_1") (pintype "passive"))
      (node (ref "R13") (pin "1") (pinfunction "1_1") (pintype "passive"))
      (node (ref "R14") (pin "1") (pinfunction "1_1") (pintype "passive"))
      (node (ref "R15") (pin "1") (pinfunction "1_1") (pintype "passive"))
      (node (ref "R2") (pin "1") (pinfunction "1_1") (pintype "passive"))
      (node (ref "R20") (pin "2") (pinfunction "2_2") (pintype "passive"))
      (node (ref "R21") (pin "2") (pinfunction "2_2") (pintype "passive"))
      (node (ref "R30") (pin "2") (pinfunction "2_2") (pintype "passive"))
      (node (ref "R32") (pin "1") (pinfunction "1_1") (pintype "passive"))
      (node (ref "R6") (pin "1") (pinfunction "1_1") (pintype "passive"))
      (node (ref "R8") (pin "1") (pinfunction "1_1") (pintype "passive"))
      (node (ref "SW1") (pin "1") (pinfunction "1_1") (pintype "passive"))
      (node (ref "T1") (pin "2") (pinfunction "2_2") (pintype "open_collector"))
      (node (ref "T2") (pin "5") (pinfunction "S1_5") (pintype "open_collector"))
      (node (ref "T3") (pin "5") (pinfunction "S1_5") (pintype "open_collector"))
      (node (ref "U1") (pin "17") (pinfunction "PGND_17") (pintype "open_collector"))
      (node (ref "U1") (pin "18") (pinfunction "PGND_18") (pintype "open_collector"))
      (node (ref "U1") (pin "25") (pinfunction "PAD_25") (pintype "open_collector"))
      (node (ref "U1") (pin "9") (pinfunction "~{CE}_9") (pintype "open_collector"))
      (node (ref "U2") (pin "10") (pinfunction "PGND_10") (pintype "open_collector"))
      (node (ref "U2") (pin "15") (pinfunction "VSEL_15") (pintype "open_collector"))
      (node (ref "U2") (pin "4") (pinfunction "GND_4") (pintype "open_collector"))
      (node (ref "U3") (pin "13") (pinfunction "PAD_13") (pintype "open_collector"))
      (node (ref "U3") (pin "3") (pinfunction "GND_3") (pintype "open_collector"))
      (node (ref "U3") (pin "4") (pinfunction "CTRL_4") (pintype "open_collector"))
      (node (ref "U4") (pin "13") (pinfunction "GND_2_13") (pintype "passive"))
      (node (ref "U4") (pin "2") (pinfunction "GND_1_2") (pintype "passive"))
      (node (ref "U5") (pin "4") (pinfunction "GND_4") (pintype "open_collector"))
      (node (ref "U6") (pin "25") (pinfunction "GND_25") (pintype "passive"))
      (node (ref "U6") (pin "27") (pinfunction "GND_27") (pintype "passive"))
      (node (ref "U6") (pin "3") (pinfunction "GND_3") (pintype "passive"))
      (node (ref "U6") (pin "44") (pinfunction "GND_44") (pintype "passive"))
      (node (ref "U6") (pin "49") (pinfunction "GND_49") (pintype "passive"))
      (node (ref "U6") (pin "50") (pinfunction "GND_50") (pintype "passive"))
      (node (ref "U6") (pin "51") (pinfunction "GND_51") (pintype "passive"))
      (node (ref "U6") (pin "52") (pinfunction "GND_52") (pintype "passive"))
      (node (ref "U6") (pin "53") (pinfunction "GND_53") (pintype "passive"))
      (node (ref "U6") (pin "54") (pinfunction "GND_54") (pintype "passive"))
      (node (ref "U6") (pin "55") (pinfunction "GND_55") (pintype "passive"))
      (node (ref "U6") (pin "56") (pinfunction "GND_56") (pintype "passive"))
      (node (ref "U6") (pin "57") (pinfunction "GND_57") (pintype "passive"))
      (node (ref "U6") (pin "7") (pinfunction "GND_7") (pintype "passive"))
    )
    (net (code "27") (name "I2C_VCC") (class "Default")
      (node (ref "P8") (pin "4") (pinfunction "4_4") (pintype "passive"))
      (node (ref "R24") (pin "2") (pinfunction "2_2") (pintype "passive"))
      (node (ref "R25") (pin "2") (pinfunction "2_2") (pintype "passive"))
      (node (ref "T3") (pin "4") (pinfunction "D2_4") (pintype "open_collector"))
    )
    (net (code "28") (name "Net-(C3-Pad1)") (class "Default")
      (node (ref "C3") (pin "1") (pinfunction "1_1") (pintype "passive"))
      (node (ref "L1") (pin "1") (pinfunction "1_1") (pintype "passive"))
      (node (ref "U1") (pin "19") (pinfunction "SW_19") (pintype "open_collector"))
      (node (ref "U1") (pin "20") (pinfunction "SW_20") (pintype "open_collector"))
    )
    (net (code "29") (name "Net-(C4-Pad1)") (class "Default")
      (node (ref "C4") (pin "1") (pinfunction "1_1") (pintype "passive"))
      (node (ref "C5") (pin "1") (pinfunction "1_1") (pintype "passive"))
      (node (ref "L1") (pin "2") (pinfunction "2_2") (pintype "passive"))
      (node (ref "U1") (pin "15") (pinfunction "SYS_15") (pintype "open_collector"))
      (node (ref "U1") (pin "16") (pinfunction "SYS_16") (pintype "open_collector"))
    )
    (net (code "30") (name "Net-(C21-Pad2)") (class "Default")
      (node (ref "C21") (pin "2") (pinfunction "2_2") (pintype "passive"))
      (node (ref "C23") (pin "2") (pinfunction "2_2") (pintype "passive"))
      (node (ref "CON2") (pin "1") (pinfunction "1_1") (pintype "open_collector"))
      (node (ref "CON4") (pin "1") (pinfunction "1_1") (pintype "open_collector"))
    )
    (net (code "31") (name "Net-(D2-ANODE)") (class "Default")
      (node (ref "D2") (pin "2") (pinfunction "ANODE_2") (pintype "passive"))
      (node (ref "R1") (pin "2") (pinfunction "2_2") (pintype "passive"))
    )
    (net (code "32") (name "Net-(D2-cathode)") (class "Default")
      (node (ref "D2") (pin "1") (pinfunction "cathode_1") (pintype "passive"))
      (node (ref "U1") (pin "4") (pinfunction "STAT_4") (pintype "open_collector"))
    )
    (net (code "33") (name "Net-(D3-ANODE)") (class "Default")
      (node (ref "D3") (pin "2") (pinfunction "ANODE_2") (pintype "passive"))
      (node (ref "P3") (pin "2") (pinfunction "2_2") (pintype "passive"))
    )
    (net (code "34") (name "Net-(D3-cathode)") (class "Default")
      (node (ref "D3") (pin "1") (pinfunction "cathode_1") (pintype "passive"))
      (node (ref "D4") (pin "2") (pinfunction "ANODE_2") (pintype "passive"))
    )
    (net (code "35") (name "Net-(D5-ANODE)") (class "Default")
      (node (ref "D5") (pin "2") (pinfunction "ANODE_2") (pintype "passive"))
      (node (ref "R12") (pin "2") (pinfunction "2_2") (pintype "passive"))
    )
    (net (code "36") (name "Net-(D6-ANODE)") (class "Default")
      (node (ref "D6") (pin "2") (pinfunction "ANODE_2") (pintype "passive"))
      (node (ref "R15") (pin "2") (pinfunction "2_2") (pintype "passive"))
      (node (ref "T1") (pin "1") (pinfunction "1_1") (pintype "open_collector"))
    )
    (net (code "37") (name "Net-(D6-cathode)") (class "Default")
      (node (ref "D6") (pin "1") (pinfunction "cathode_1") (pintype "passive"))
      (node (ref "R10") (pin "2") (pinfunction "2_2") (pintype "passive"))
      (node (ref "R5") (pin "1") (pinfunction "1_1") (pintype "passive"))
    )
    (net (code "38") (name "Net-(F1-Pad2)") (class "Default")
      (node (ref "F1") (pin "2") (pinfunction "2_2") (pintype "open_collector"))
      (node (ref "P1") (pin "1") (pinfunction "1_1") (pintype "passive"))
    )
    (net (code "39") (name "Net-(P6-Pad3)") (class "Default")
      (node (ref "P6") (pin "3") (pinfunction "3_3") (pintype "passive"))
      (node (ref "R26") (pin "1") (pinfunction "1_1") (pintype "passive"))
    )
    (net (code "40") (name "Net-(P6-Pad5)") (class "Default")
      (node (ref "P6") (pin "5") (pinfunction "5_5") (pintype "passive"))
      (node (ref "R27") (pin "1") (pinfunction "1_1") (pintype "passive"))
    )
    (net (code "41") (name "Net-(R14-Pad2)") (class "Default")
      (node (ref "R14") (pin "2") (pinfunction "2_2") (pintype "passive"))
      (node (ref "R7") (pin "1") (pinfunction "1_1") (pintype "passive"))
      (node (ref "T1") (pin "3") (pinfunction "3_3") (pintype "open_collector"))
    )
    (net (code "42") (name "Net-(T2-D1)") (class "Default")
      (node (ref "R18") (pin "2") (pinfunction "2_2") (pintype "passive"))
      (node (ref "T2") (pin "6") (pinfunction "D1_6") (pintype "open_collector"))
    )
    (net (code "43") (name "Net-(T2-G1)") (class "Default")
      (node (ref "R19") (pin "1") (pinfunction "1_1") (pintype "passive"))
      (node (ref "R20") (pin "1") (pinfunction "1_1") (pintype "passive"))
      (node (ref "T2") (pin "1") (pinfunction "G1_1") (pintype "open_collector"))
    )
    (net (code "44") (name "Net-(T2-G2)") (class "Default")
      (node (ref "R17") (pin "2") (pinfunction "2_2") (pintype "passive"))
      (node (ref "R18") (pin "1") (pinfunction "1_1") (pintype "passive"))
      (node (ref "T2") (pin "3") (pinfunction "G2_3") (pintype "open_collector"))
    )
    (net (code "45") (name "Net-(T2-S2)") (class "Default")
      (node (ref "J1") (pin "3") (pinfunction "3_3") (pintype "open_collector"))
      (node (ref "R17") (pin "1") (pinfunction "1_1") (pintype "passive"))
      (node (ref "T2") (pin "2") (pinfunction "S2_2") (pintype "open_collector"))
    )
    (net (code "46") (name "Net-(T3-D1)") (class "Default")
      (node (ref "R35") (pin "2") (pinfunction "2_2") (pintype "passive"))
      (node (ref "T3") (pin "6") (pinfunction "D1_6") (pintype "open_collector"))
    )
    (net (code "47") (name "Net-(T3-G1)") (class "Default")
      (node (ref "R30") (pin "1") (pinfunction "1_1") (pintype "passive"))
      (node (ref "R31") (pin "1") (pinfunction "1_1") (pintype "passive"))
      (node (ref "T3") (pin "1") (pinfunction "G1_1") (pintype "open_collector"))
    )
    (net (code "48") (name "Net-(T3-G2)") (class "Default")
      (node (ref "R35") (pin "1") (pinfunction "1_1") (pintype "passive"))
      (node (ref "R36") (pin "1") (pinfunction "1_1") (pintype "passive"))
      (node (ref "T3") (pin "3") (pinfunction "G2_3") (pintype "open_collector"))
    )
    (net (code "49") (name "Net-(U1-BTST)") (class "Default")
      (node (ref "C3") (pin "2") (pinfunction "2_2") (pintype "passive"))
      (node (ref "U1") (pin "21") (pinfunction "BTST_21") (pintype "open_collector"))
    )
    (net (code "50") (name "Net-(U1-ILIM)") (class "Default")
      (node (ref "R7") (pin "2") (pinfunction "2_2") (pintype "passive"))
      (node (ref "U1") (pin "10") (pinfunction "ILIM_10") (pintype "open_collector"))
    )
    (net (code "51") (name "Net-(U1-OTG)") (class "Default")
      (node (ref "R11") (pin "2") (pinfunction "2_2") (pintype "passive"))
      (node (ref "U1") (pin "8") (pinfunction "OTG_8") (pintype "open_collector"))
    )
    (net (code "52") (name "Net-(U1-PMID)") (class "Default")
      (node (ref "C1") (pin "1") (pinfunction "1_1") (pintype "passive"))
      (node (ref "U1") (pin "23") (pinfunction "PMID_23") (pintype "open_collector"))
    )
    (net (code "53") (name "Net-(U1-PSEL)") (class "Default")
      (node (ref "R2") (pin "2") (pinfunction "2_2") (pintype "passive"))
      (node (ref "U1") (pin "2") (pinfunction "PSEL_2") (pintype "open_collector"))
    )
    (net (code "54") (name "Net-(U1-REGN)") (class "Default")
      (node (ref "C2") (pin "1") (pinfunction "1_1") (pintype "passive"))
      (node (ref "R3") (pin "2") (pinfunction "2_2") (pintype "passive"))
      (node (ref "U1") (pin "22") (pinfunction "REGN_22") (pintype "open_collector"))
    )
    (net (code "55") (name "Net-(U1-TS)") (class "Default")
      (node (ref "R13") (pin "2") (pinfunction "2_2") (pintype "passive"))
      (node (ref "R3") (pin "1") (pinfunction "1_1") (pintype "passive"))
      (node (ref "R6") (pin "2") (pinfunction "2_2") (pintype "passive"))
      (node (ref "U1") (pin "11") (pinfunction "TS_11") (pintype "open_collector"))
    )
    (net (code "56") (name "Net-(U2-FB)") (class "Default")
      (node (ref "R4") (pin "1") (pinfunction "1_1") (pintype "passive"))
      (node (ref "R8") (pin "2") (pinfunction "2_2") (pintype "passive"))
      (node (ref "U2") (pin "5") (pinfunction "FB_5") (pintype "open_collector"))
    )
    (net (code "57") (name "Net-(U2-L1)") (class "Default")
      (node (ref "L2") (pin "1") (pinfunction "1_1") (pintype "passive"))
      (node (ref "U2") (pin "11") (pinfunction "L1_11") (pintype "open_collector"))
    )
    (net (code "58") (name "Net-(U2-L2)") (class "Default")
      (node (ref "L2") (pin "2") (pinfunction "2_2") (pintype "passive"))
      (node (ref "U2") (pin "9") (pinfunction "L2_9") (pintype "open_collector"))
    )
    (net (code "59") (name "Net-(U2-PS{slash}S)") (class "Default")
      (node (ref "R9") (pin "2") (pinfunction "2_2") (pintype "passive"))
      (node (ref "U2") (pin "1") (pinfunction "PS/S_1") (pintype "open_collector"))
    )
    (net (code "60") (name "Net-(U2-VAUX)") (class "Default")
      (node (ref "C12") (pin "2") (pinfunction "2_2") (pintype "passive"))
      (node (ref "U2") (pin "3") (pinfunction "VAUX_3") (pintype "open_collector"))
    )
    (net (code "61") (name "Net-(U3-SW)") (class "Default")
      (node (ref "L3") (pin "1") (pinfunction "1_1") (pintype "passive"))
      (node (ref "U3") (pin "2") (pinfunction "SW_2") (pintype "open_collector"))
    )
    (net (code "62") (name "Net-(U4-RST_N)") (class "Default")
      (node (ref "C16") (pin "2") (pinfunction "2_2") (pintype "passive"))
      (node (ref "R28") (pin "1") (pinfunction "1_1") (pintype "passive"))
      (node (ref "U4") (pin "10") (pinfunction "RST_N_10") (pintype "passive"))
    )
    (net (code "63") (name "Net-(U5-VBAT)") (class "Default")
      (node (ref "CON3") (pin "POS") (pinfunction "POS_POS") (pintype "passive"))
      (node (ref "U5") (pin "3") (pinfunction "VBAT_3") (pintype "open_collector"))
    )
    (net (code "64") (name "Net-(U5-X1)") (class "Default")
      (node (ref "U5") (pin "1") (pinfunction "X1_1") (pintype "open_collector"))
      (node (ref "X1") (pin "2") (pinfunction "2_2") (pintype "passive"))
    )
    (net (code "65") (name "Net-(U5-X2)") (class "Default")
      (node (ref "U5") (pin "2") (pinfunction "X2_2") (pintype "open_collector"))
      (node (ref "X1") (pin "1") (pinfunction "1_1") (pintype "passive"))
    )
    (net (code "66") (name "Net-(U6-BOOT0)") (class "Default")
      (node (ref "R21") (pin "1") (pinfunction "1_1") (pintype "passive"))
      (node (ref "U6") (pin "43") (pinfunction "BOOT0_43") (pintype "passive"))
    )
    (net (code "67") (name "Net-(U6-DBG_SX1276_DIO1)") (class "Default")
      (node (ref "TP5") (pin "1") (pinfunction "1_1") (pintype "passive"))
      (node (ref "U6") (pin "12") (pinfunction "DBG_SX1276_DIO1_12") (pintype "passive"))
    )
    (net (code "68") (name "Net-(U6-DBG_SX1276_DIO2)") (class "Default")
      (node (ref "TP1") (pin "1") (pinfunction "1_1") (pintype "passive"))
      (node (ref "U6") (pin "8") (pinfunction "DBG_SX1276_DIO2_8") (pintype "passive"))
    )
    (net (code "69") (name "Net-(U6-DBG_SX1276_DIO3)") (class "Default")
      (node (ref "TP2") (pin "1") (pinfunction "1_1") (pintype "passive"))
      (node (ref "U6") (pin "9") (pinfunction "DBG_SX1276_DIO3_9") (pintype "passive"))
    )
    (net (code "70") (name "Net-(U6-DBG_SX1276_DIO5)") (class "Default")
      (node (ref "TP4") (pin "1") (pinfunction "1_1") (pintype "passive"))
      (node (ref "U6") (pin "11") (pinfunction "DBG_SX1276_DIO5_11") (pintype "passive"))
    )
    (net (code "71") (name "Net-(U6-PA5{slash}ADC5{slash}DAC2)") (class "Default")
      (node (ref "R29") (pin "1") (pinfunction "1_1") (pintype "passive"))
      (node (ref "R32") (pin "2") (pinfunction "2_2") (pintype "passive"))
      (node (ref "U6") (pin "21") (pinfunction "PA5/ADC5/DAC2_21") (pintype "passive"))
    )
    (net (code "72") (name "Net-(U6-PA12{slash}USB_DP)") (class "Default")
      (node (ref "R22") (pin "1") (pinfunction "1_1") (pintype "passive"))
      (node (ref "U6") (pin "1") (pinfunction "PA12/USB_DP_1") (pintype "passive"))
    )
    (net (code "73") (name "Net-(U6-SX1276_DIO4)") (class "Default")
      (node (ref "TP3") (pin "1") (pinfunction "1_1") (pintype "passive"))
      (node (ref "U6") (pin "10") (pinfunction "SX1276_DIO4_10") (pintype "passive"))
    )
    (net (code "74") (name "Net-(U6-TCXO_VCC)") (class "Default")
      (node (ref "R22") (pin "2") (pinfunction "2_2") (pintype "passive"))
      (node (ref "U6") (pin "48") (pinfunction "TCXO_VCC_48") (pintype "passive"))
    )
    (net (code "75") (name "VBAT") (class "Default")
      (node (ref "C13") (pin "2") (pinfunction "2_2") (pintype "passive"))
      (node (ref "C6") (pin "2") (pinfunction "2_2") (pintype "passive"))
      (node (ref "C7") (pin "2") (pinfunction "2_2") (pintype "passive"))
      (node (ref "C8") (pin "2") (pinfunction "2_2") (pintype "passive"))
      (node (ref "D1") (pin "1") (pinfunction "cathode_1") (pintype "passive"))
      (node (ref "F1") (pin "1") (pinfunction "1_1") (pintype "open_collector"))
      (node (ref "J1") (pin "1") (pinfunction "1_1") (pintype "open_collector"))
      (node (ref "R29") (pin "2") (pinfunction "2_2") (pintype "passive"))
      (node (ref "R9") (pin "1") (pinfunction "1_1") (pintype "passive"))
      (node (ref "U1") (pin "13") (pinfunction "BAT_13") (pintype "open_collector"))
      (node (ref "U1") (pin "14") (pinfunction "BAT_14") (pintype "open_collector"))
      (node (ref "U2") (pin "12") (pinfunction "VIN_12") (pintype "open_collector"))
      (node (ref "U2") (pin "13") (pinfunction "VIN_13") (pintype "open_collector"))
      (node (ref "U3") (pin "1") (pinfunction "VIN_1") (pintype "open_collector"))
      (node (ref "U3") (pin "10") (pinfunction "VSEL2_10") (pintype "open_collector"))
      (node (ref "U3") (pin "11") (pinfunction "VSEL1_11") (pintype "open_collector"))
      (node (ref "U3") (pin "12") (pinfunction "EN_12") (pintype "open_collector"))
      (node (ref "U3") (pin "8") (pinfunction "VSEL4_8") (pintype "open_collector"))
      (node (ref "U3") (pin "9") (pinfunction "VSEL3_9") (pintype "open_collector"))
    )
    (net (code "76") (name "VCC") (class "Default")
      (node (ref "C14") (pin "2") (pinfunction "2_2") (pintype "passive"))
      (node (ref "C17") (pin "2") (pinfunction "2_2") (pintype "passive"))
      (node (ref "C18") (pin "2") (pinfunction "2_2") (pintype "passive"))
      (node (ref "C19") (pin "2") (pinfunction "2_2") (pintype "passive"))
      (node (ref "C24") (pin "2") (pinfunction "2_2") (pintype "passive"))
      (node (ref "L3") (pin "2") (pinfunction "2_2") (pintype "passive"))
      (node (ref "P5") (pin "2") (pinfunction "2_2") (pintype "passive"))
      (node (ref "R23") (pin "2") (pinfunction "2_2") (pintype "passive"))
      (node (ref "R28") (pin "2") (pinfunction "2_2") (pintype "passive"))
      (node (ref "R36") (pin "2") (pinfunction "2_2") (pintype "passive"))
      (node (ref "T3") (pin "2") (pinfunction "S2_2") (pintype "open_collector"))
      (node (ref "U3") (pin "5") (pinfunction "VOUT_5") (pintype "open_collector"))
      (node (ref "U4") (pin "14") (pinfunction "VBAT_14") (pintype "passive"))
      (node (ref "U5") (pin "8") (pinfunction "VDD_8") (pintype "open_collector"))
      (node (ref "U6") (pin "4") (pinfunction "VDD_USB_4") (pintype "passive"))
      (node (ref "U6") (pin "5") (pinfunction "VDD_MCU_5") (pintype "passive"))
      (node (ref "U6") (pin "6") (pinfunction "VDD_RF_6") (pintype "passive"))
    )
    (net (code "77") (name "unconnected-(CON1-P2-Pad2)") (class "Default")
      (node (ref "CON1") (pin "2") (pinfunction "P2_2") (pintype "passive+no_connect"))
    )
    (net (code "78") (name "unconnected-(CON1-P3-Pad3)") (class "Default")
      (node (ref "CON1") (pin "3") (pinfunction "P3_3") (pintype "passive+no_connect"))
    )
    (net (code "79") (name "unconnected-(CON1-P4-Pad4)") (class "Default")
      (node (ref "CON1") (pin "4") (pinfunction "P4_4") (pintype "passive+no_connect"))
    )
    (net (code "80") (name "unconnected-(P6-Pad1)") (class "Default")
      (node (ref "P6") (pin "1") (pinfunction "1_1") (pintype "passive+no_connect"))
    )
    (net (code "81") (name "unconnected-(P6-Pad7)") (class "Default")
      (node (ref "P6") (pin "7") (pinfunction "7_7") (pintype "passive+no_connect"))
    )
    (net (code "82") (name "unconnected-(P6-Pad11)") (class "Default")
      (node (ref "P6") (pin "11") (pinfunction "11_11") (pintype "passive+no_connect"))
    )
    (net (code "83") (name "unconnected-(P6-Pad12)") (class "Default")
      (node (ref "P6") (pin "12") (pinfunction "12_12") (pintype "passive+no_connect"))
    )
    (net (code "84") (name "unconnected-(P6-Pad13)") (class "Default")
      (node (ref "P6") (pin "13") (pinfunction "13_13") (pintype "passive+no_connect"))
    )
    (net (code "85") (name "unconnected-(P6-Pad15)") (class "Default")
      (node (ref "P6") (pin "15") (pinfunction "15_15") (pintype "passive+no_connect"))
    )
    (net (code "86") (name "unconnected-(P6-Pad16)") (class "Default")
      (node (ref "P6") (pin "16") (pinfunction "16_16") (pintype "passive+no_connect"))
    )
    (net (code "87") (name "unconnected-(P6-Pad17)") (class "Default")
      (node (ref "P6") (pin "17") (pinfunction "17_17") (pintype "passive+no_connect"))
    )
    (net (code "88") (name "unconnected-(P6-Pad18)") (class "Default")
      (node (ref "P6") (pin "18") (pinfunction "18_18") (pintype "passive+no_connect"))
    )
    (net (code "89") (name "unconnected-(P6-Pad26)") (class "Default")
      (node (ref "P6") (pin "26") (pinfunction "26_26") (pintype "passive+no_connect"))
    )
    (net (code "90") (name "unconnected-(P6-Pad27)") (class "Default")
      (node (ref "P6") (pin "27") (pinfunction "27_27") (pintype "passive+no_connect"))
    )
    (net (code "91") (name "unconnected-(P6-Pad28)") (class "Default")
      (node (ref "P6") (pin "28") (pinfunction "28_28") (pintype "passive+no_connect"))
    )
    (net (code "92") (name "unconnected-(P6-Pad32)") (class "Default")
      (node (ref "P6") (pin "32") (pinfunction "32_32") (pintype "passive+no_connect"))
    )
    (net (code "93") (name "unconnected-(P6-Pad33)") (class "Default")
      (node (ref "P6") (pin "33") (pinfunction "33_33") (pintype "passive+no_connect"))
    )
    (net (code "94") (name "unconnected-(P6-Pad35)") (class "Default")
      (node (ref "P6") (pin "35") (pinfunction "35_35") (pintype "passive+no_connect"))
    )
    (net (code "95") (name "unconnected-(P6-Pad36)") (class "Default")
      (node (ref "P6") (pin "36") (pinfunction "36_36") (pintype "passive+no_connect"))
    )
    (net (code "96") (name "unconnected-(P6-Pad37)") (class "Default")
      (node (ref "P6") (pin "37") (pinfunction "37_37") (pintype "passive+no_connect"))
    )
    (net (code "97") (name "unconnected-(P6-Pad38)") (class "Default")
      (node (ref "P6") (pin "38") (pinfunction "38_38") (pintype "passive+no_connect"))
    )
    (net (code "98") (name "unconnected-(P6-Pad40)") (class "Default")
      (node (ref "P6") (pin "40") (pinfunction "40_40") (pintype "passive+no_connect"))
    )
    (net (code "99") (name "unconnected-(SW1-Pad2)") (class "Default")
      (node (ref "SW1") (pin "2") (pinfunction "2_2") (pintype "passive"))
    )
    (net (code "100") (name "unconnected-(SW1-Pad3)") (class "Default")
      (node (ref "SW1") (pin "3") (pinfunction "3_3") (pintype "passive"))
    )
    (net (code "101") (name "unconnected-(U1-INT-Pad7)") (class "Default")
      (node (ref "U1") (pin "7") (pinfunction "INT_7") (pintype "open_collector+no_connect"))
    )
    (net (code "102") (name "unconnected-(U1-QON-Pad12)") (class "Default")
      (node (ref "U1") (pin "12") (pinfunction "QON_12") (pintype "open_collector+no_connect"))
    )
    (net (code "103") (name "unconnected-(U1-~{PG}-Pad3)") (class "Default")
      (node (ref "U1") (pin "3") (pinfunction "~{PG}_3") (pintype "open_collector+no_connect"))
    )
    (net (code "104") (name "unconnected-(U2-FB2-Pad6)") (class "Default")
      (node (ref "U2") (pin "6") (pinfunction "FB2_6") (pintype "open_collector+no_connect"))
    )
    (net (code "105") (name "unconnected-(U2-PG-Pad2)") (class "Default")
      (node (ref "U2") (pin "2") (pinfunction "PG_2") (pintype "open_collector+no_connect"))
    )
    (net (code "106") (name "unconnected-(U3-LOAD-Pad6)") (class "Default")
      (node (ref "U3") (pin "6") (pinfunction "LOAD_6") (pintype "open_collector+no_connect"))
    )
    (net (code "107") (name "unconnected-(U3-PG-Pad7)") (class "Default")
      (node (ref "U3") (pin "7") (pinfunction "PG_7") (pintype "open_collector+no_connect"))
    )
    (net (code "108") (name "unconnected-(U4-NC-Pad1)") (class "Default")
      (node (ref "U4") (pin "1") (pinfunction "NC_1") (pintype "passive+no_connect"))
    )
    (net (code "109") (name "unconnected-(U4-P0_0-Pad11)") (class "Default")
      (node (ref "U4") (pin "11") (pinfunction "P0_0_11") (pintype "passive+no_connect"))
    )
    (net (code "110") (name "unconnected-(U4-P0_2-Pad12)") (class "Default")
      (node (ref "U4") (pin "12") (pinfunction "P0_2_12") (pintype "passive+no_connect"))
    )
    (net (code "111") (name "unconnected-(U4-P1_2-Pad3)") (class "Default")
      (node (ref "U4") (pin "3") (pinfunction "P1_2_3") (pintype "passive+no_connect"))
    )
    (net (code "112") (name "unconnected-(U4-P1_3-Pad4)") (class "Default")
      (node (ref "U4") (pin "4") (pinfunction "P1_3_4") (pintype "passive+no_connect"))
    )
    (net (code "113") (name "unconnected-(U4-P1_7-Pad5)") (class "Default")
      (node (ref "U4") (pin "5") (pinfunction "P1_7_5") (pintype "passive+no_connect"))
    )
    (net (code "114") (name "unconnected-(U4-P3_6-Pad9)") (class "Default")
      (node (ref "U4") (pin "9") (pinfunction "P3_6_9") (pintype "passive+no_connect"))
    )
    (net (code "115") (name "unconnected-(U5-~{IRQ}{slash}FOUT-Pad7)") (class "Default")
      (node (ref "U5") (pin "7") (pinfunction "~{IRQ}/FOUT_7") (pintype "open_collector+no_connect"))
    )
    (net (code "116") (name "unconnected-(U6-DBG_CRF1-Pad28)") (class "Default")
      (node (ref "U6") (pin "28") (pinfunction "DBG_CRF1_28") (pintype "passive+no_connect"))
    )
    (net (code "117") (name "unconnected-(U6-DBG_CRF2-Pad30)") (class "Default")
      (node (ref "U6") (pin "30") (pinfunction "DBG_CRF2_30") (pintype "passive+no_connect"))
    )
    (net (code "118") (name "unconnected-(U6-DBG_CRF3-Pad29)") (class "Default")
      (node (ref "U6") (pin "29") (pinfunction "DBG_CRF3_29") (pintype "passive+no_connect"))
    )
    (net (code "119") (name "unconnected-(U6-DBG_SX1276_DIO0-Pad13)") (class "Default")
      (node (ref "U6") (pin "13") (pinfunction "DBG_SX1276_DIO0_13") (pintype "passive+no_connect"))
    )
    (net (code "120") (name "unconnected-(U6-PH0-OSC_IN-Pad46)") (class "Default")
      (node (ref "U6") (pin "46") (pinfunction "PH0-OSC_IN_46") (pintype "passive+no_connect"))
    )
    (net (code "121") (name "unconnected-(U6-PH1-OSC_OUT-Pad45)") (class "Default")
      (node (ref "U6") (pin "45") (pinfunction "PH1-OSC_OUT_45") (pintype "passive+no_connect"))
    )
    (net (code "122") (name "unconnected-(U6-STSAFE_nRST-Pad31)") (class "Default")
      (node (ref "U6") (pin "31") (pinfunction "STSAFE_nRST_31") (pintype "passive+no_connect"))
    )
    (net (code "123") (name "unconnected-(U6-TCXO_OUT-Pad47)") (class "Default")
      (node (ref "U6") (pin "47") (pinfunction "TCXO_OUT_47") (pintype "passive+no_connect"))
    )
    (net (code "124") (name "unconnected-(U6-VREF+-Pad32)") (class "Default")
      (node (ref "U6") (pin "32") (pinfunction "VREF+_32") (pintype "passive+no_connect"))
    )
  )
)
